# base.net
KiCad netlist of a schematic drawn in EAGLE
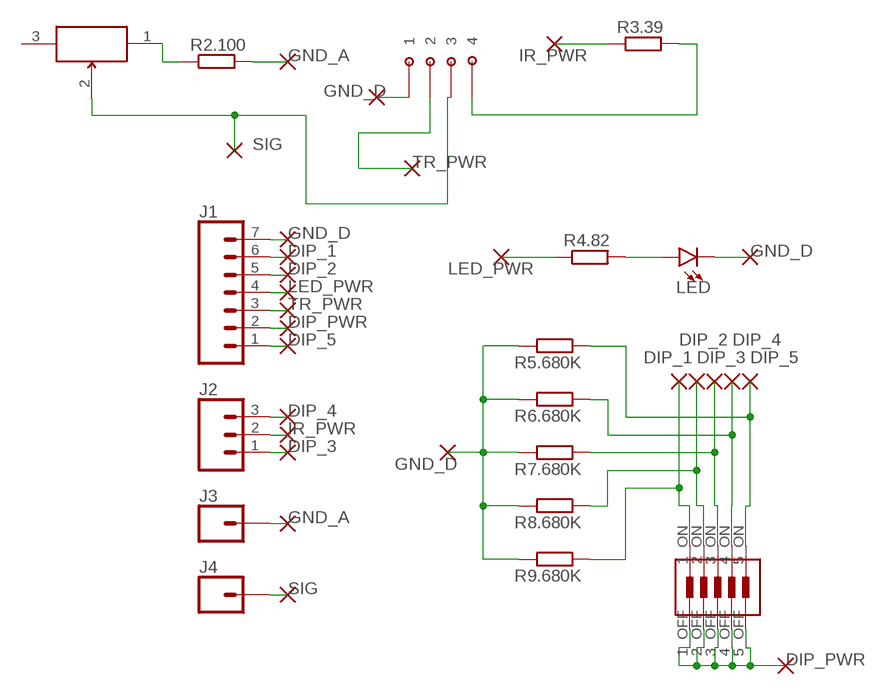
[diagram p0: schematic, sheet 1]

(export (version "E")
  (design (tool "Eeschema 10.0.6"))
  (components
    (comp (ref "J1")
      (value "CONN_07")
      (footprint "eagle-import:1X07")
      (libsource (lib "eagle-import") (part "CONN_07"))
    )
    (comp (ref "J2")
      (value "CONN_03")
      (footprint "eagle-import:1X03")
      (libsource (lib "eagle-import") (part "CONN_03"))
    )
    (comp (ref "J3")
      (value "CONN_01")
      (footprint "eagle-import:1X01")
      (libsource (lib "eagle-import") (part "CONN_01"))
    )
    (comp (ref "J4")
      (value "CONN_01")
      (footprint "eagle-import:1X01")
      (libsource (lib "eagle-import") (part "CONN_01"))
    )
    (comp (ref "LED")
      (value "LED-3MM-NO_SILK")
      (footprint "eagle-import:LED_3MM-NS")
      (libsource (lib "eagle-import") (part "LED-3MM-NO_SILK"))
    )
    (comp (ref "R2.100")
      (value "R-EU_0204/7")
      (footprint "eagle-import:0204_7")
      (libsource (lib "eagle-import") (part "R-EU_0204/7"))
    )
    (comp (ref "R3.39")
      (value "R-EU_0204/7")
      (footprint "eagle-import:0204_7")
      (libsource (lib "eagle-import") (part "R-EU_0204/7"))
    )
    (comp (ref "R4.82")
      (value "R-EU_0204/7")
      (footprint "eagle-import:0204_7")
      (libsource (lib "eagle-import") (part "R-EU_0204/7"))
    )
    (comp (ref "R5.680K")
      (value "R-EU_0204/7")
      (footprint "eagle-import:0204_7")
      (libsource (lib "eagle-import") (part "R-EU_0204/7"))
    )
    (comp (ref "R6.680K")
      (value "R-EU_0204/7")
      (footprint "eagle-import:0204_7")
      (libsource (lib "eagle-import") (part "R-EU_0204/7"))
    )
    (comp (ref "R7.680K")
      (value "R-EU_0204/7")
      (footprint "eagle-import:0204_7")
      (libsource (lib "eagle-import") (part "R-EU_0204/7"))
    )
    (comp (ref "R8.680K")
      (value "R-EU_0204/7")
      (footprint "eagle-import:0204_7")
      (libsource (lib "eagle-import") (part "R-EU_0204/7"))
    )
    (comp (ref "R9.680K")
      (value "R-EU_0204/7")
      (footprint "eagle-import:0204_7")
      (libsource (lib "eagle-import") (part "R-EU_0204/7"))
    )
    (comp (ref "U$1")
      (value "DF1BZ-4DP-2.5DS")
      (footprint "eagle-import:DF1BZ-4DP-2.5DS")
      (libsource (lib "eagle-import") (part "DF1BZ-4DP-2.5DS"))
    )
    (comp (ref "U$2")
      (value "DIP-SW-CTS-208-5")
      (footprint "eagle-import:DIP-SW-CTS-208-5")
      (libsource (lib "eagle-import") (part "DIP-SW-CTS-208-5"))
    )
    (comp (ref "U$3")
      (value "CT6EP103")
      (footprint "eagle-import:CT6EP103")
      (libsource (lib "eagle-import") (part "CT6EP103"))
    )
  )
  (nets
    (net (code "1") (name "/DIP_1") (class "Default")
      (node (ref "J1") (pin "6") (pinfunction "6_6") (pintype "passive"))
      (node (ref "R9.680K") (pin "1") (pinfunction "1_1") (pintype "passive"))
      (node (ref "U$2") (pin "1_ON") (pinfunction "1_ON_1_ON") (pintype "bidirectional"))
    )
    (net (code "2") (name "/DIP_2") (class "Default")
      (node (ref "J1") (pin "5") (pinfunction "5_5") (pintype "passive"))
      (node (ref "R8.680K") (pin "1") (pinfunction "1_1") (pintype "passive"))
      (node (ref "U$2") (pin "2_ON") (pinfunction "2_ON_2_ON") (pintype "bidirectional"))
    )
    (net (code "3") (name "/DIP_3") (class "Default")
      (node (ref "J2") (pin "1") (pinfunction "1_1") (pintype "passive"))
      (node (ref "R7.680K") (pin "1") (pinfunction "1_1") (pintype "passive"))
      (node (ref "U$2") (pin "3_ON") (pinfunction "3_ON_3_ON") (pintype "bidirectional"))
    )
    (net (code "4") (name "/DIP_4") (class "Default")
      (node (ref "J2") (pin "3") (pinfunction "3_3") (pintype "passive"))
      (node (ref "R6.680K") (pin "1") (pinfunction "1_1") (pintype "passive"))
      (node (ref "U$2") (pin "4_ON") (pinfunction "4_ON_4_ON") (pintype "bidirectional"))
    )
    (net (code "5") (name "/DIP_5") (class "Default")
      (node (ref "J1") (pin "1") (pinfunction "1_1") (pintype "passive"))
      (node (ref "R5.680K") (pin "1") (pinfunction "1_1") (pintype "passive"))
      (node (ref "U$2") (pin "5_ON") (pinfunction "5_ON_5_ON") (pintype "bidirectional"))
    )
    (net (code "6") (name "/DIP_PWR") (class "Default")
      (node (ref "J1") (pin "2") (pinfunction "2_2") (pintype "passive"))
      (node (ref "U$2") (pin "1_OFF") (pinfunction "1_OFF_1_OFF") (pintype "bidirectional"))
      (node (ref "U$2") (pin "2_OFF") (pinfunction "2_OFF_2_OFF") (pintype "bidirectional"))
      (node (ref "U$2") (pin "3_OFF") (pinfunction "3_OFF_3_OFF") (pintype "bidirectional"))
      (node (ref "U$2") (pin "4_OFF") (pinfunction "4_OFF_4_OFF") (pintype "bidirectional"))
      (node (ref "U$2") (pin "5_OFF") (pinfunction "5_OFF_5_OFF") (pintype "bidirectional"))
    )
    (net (code "7") (name "/GND_A") (class "Default")
      (node (ref "J3") (pin "1") (pinfunction "1_1") (pintype "passive"))
      (node (ref "R2.100") (pin "2") (pinfunction "2_2") (pintype "passive"))
    )
    (net (code "8") (name "/GND_D") (class "Default")
      (node (ref "J1") (pin "7") (pinfunction "7_7") (pintype "passive"))
      (node (ref "LED") (pin "K") (pinfunction "C_K") (pintype "passive"))
      (node (ref "R5.680K") (pin "2") (pinfunction "2_2") (pintype "passive"))
      (node (ref "R6.680K") (pin "2") (pinfunction "2_2") (pintype "passive"))
      (node (ref "R7.680K") (pin "2") (pinfunction "2_2") (pintype "passive"))
      (node (ref "R8.680K") (pin "2") (pinfunction "2_2") (pintype "passive"))
      (node (ref "R9.680K") (pin "2") (pinfunction "2_2") (pintype "passive"))
      (node (ref "U$1") (pin "1") (pinfunction "1_1") (pintype "power_in"))
    )
    (net (code "9") (name "/IR_PWR") (class "Default")
      (node (ref "J2") (pin "2") (pinfunction "2_2") (pintype "passive"))
      (node (ref "R3.39") (pin "1") (pinfunction "1_1") (pintype "passive"))
    )
    (net (code "10") (name "/LED_PWR") (class "Default")
      (node (ref "J1") (pin "4") (pinfunction "4_4") (pintype "passive"))
      (node (ref "R4.82") (pin "1") (pinfunction "1_1") (pintype "passive"))
    )
    (net (code "11") (name "/P$1") (class "Default")
      (node (ref "U$3") (pin "3") (pinfunction "P$1_3") (pintype "power_in"))
    )
    (net (code "12") (name "/SIG") (class "Default")
      (node (ref "J4") (pin "1") (pinfunction "1_1") (pintype "passive"))
      (node (ref "U$1") (pin "3") (pinfunction "3_3") (pintype "power_in"))
      (node (ref "U$3") (pin "2") (pinfunction "P$2_2") (pintype "power_in"))
    )
    (net (code "13") (name "/TR_PWR") (class "Default")
      (node (ref "J1") (pin "3") (pinfunction "3_3") (pintype "passive"))
      (node (ref "U$1") (pin "2") (pinfunction "2_2") (pintype "power_in"))
    )
    (net (code "14") (name "Net-(LED-PadA)") (class "Default")
      (node (ref "LED") (pin "A") (pinfunction "A_A") (pintype "passive"))
      (node (ref "R4.82") (pin "2") (pinfunction "2_2") (pintype "passive"))
    )
    (net (code "15") (name "Net-(R3.39-Pad2)") (class "Default")
      (node (ref "R3.39") (pin "2") (pinfunction "2_2") (pintype "passive"))
      (node (ref "U$1") (pin "4") (pinfunction "4_4") (pintype "power_in"))
    )
    (net (code "16") (name "Net-(U$3-P$3)") (class "Default")
      (node (ref "R2.100") (pin "1") (pinfunction "1_1") (pintype "passive"))
      (node (ref "U$3") (pin "1") (pinfunction "P$3_1") (pintype "power_in"))
    )
  )
)
